# Bolt.net
KiCad netlist of a schematic drawn in EAGLE
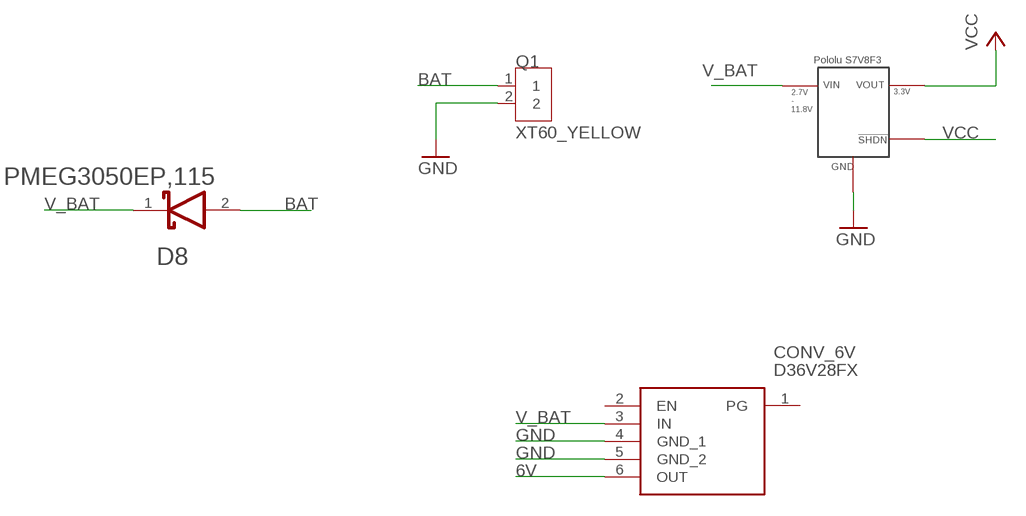
[diagram p0: schematic, sheet 1]
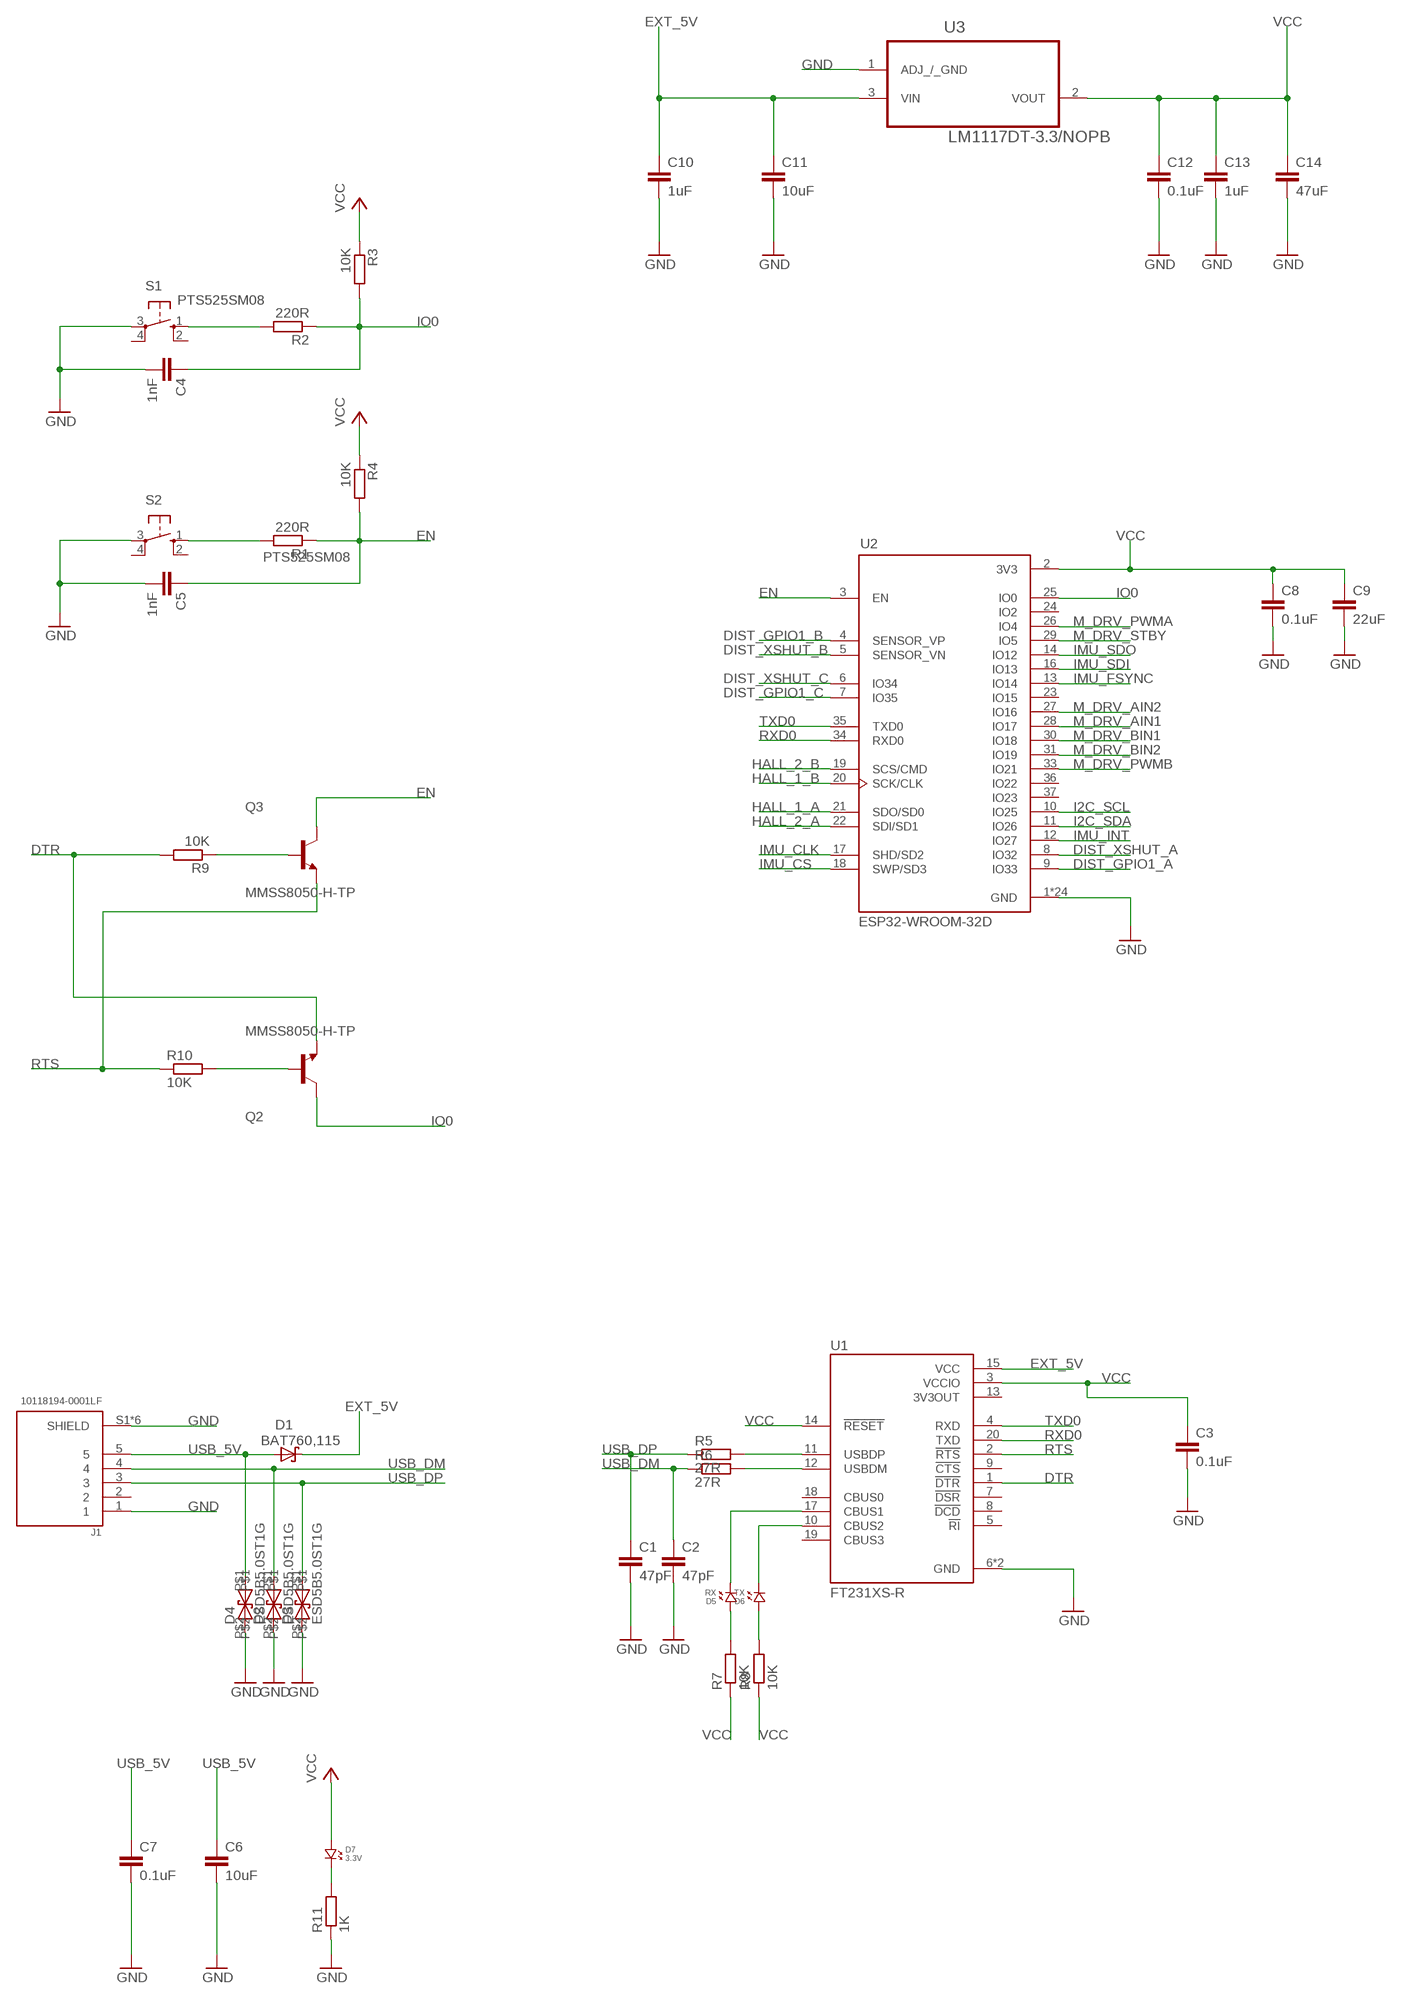
[diagram p1: schematic, sheet 2]
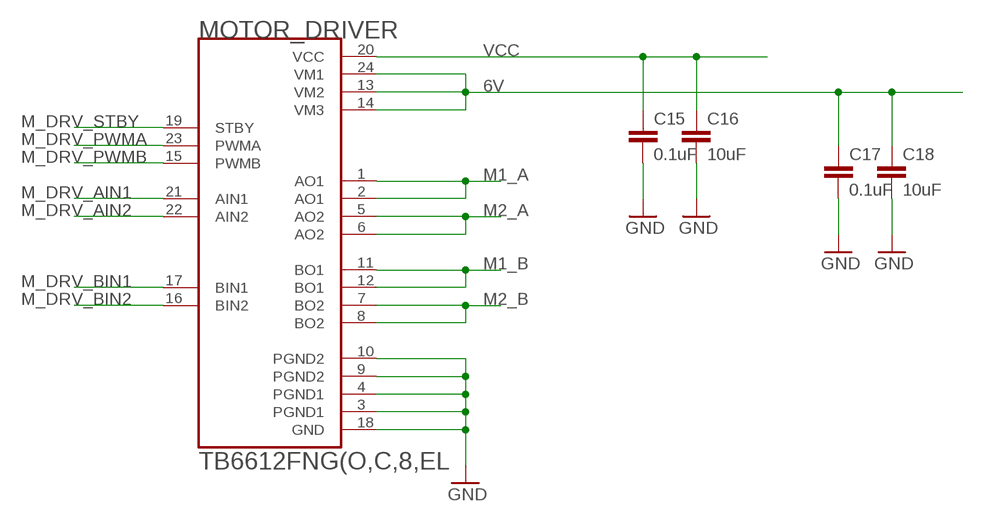
[diagram p2: schematic, sheet 3]
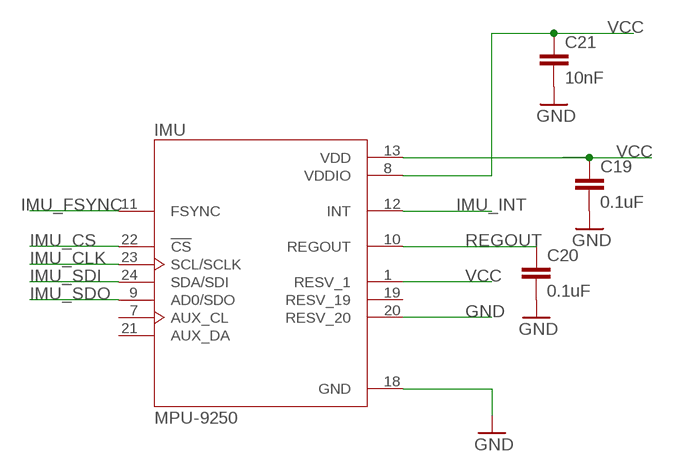
[diagram p3: schematic, sheet 4]
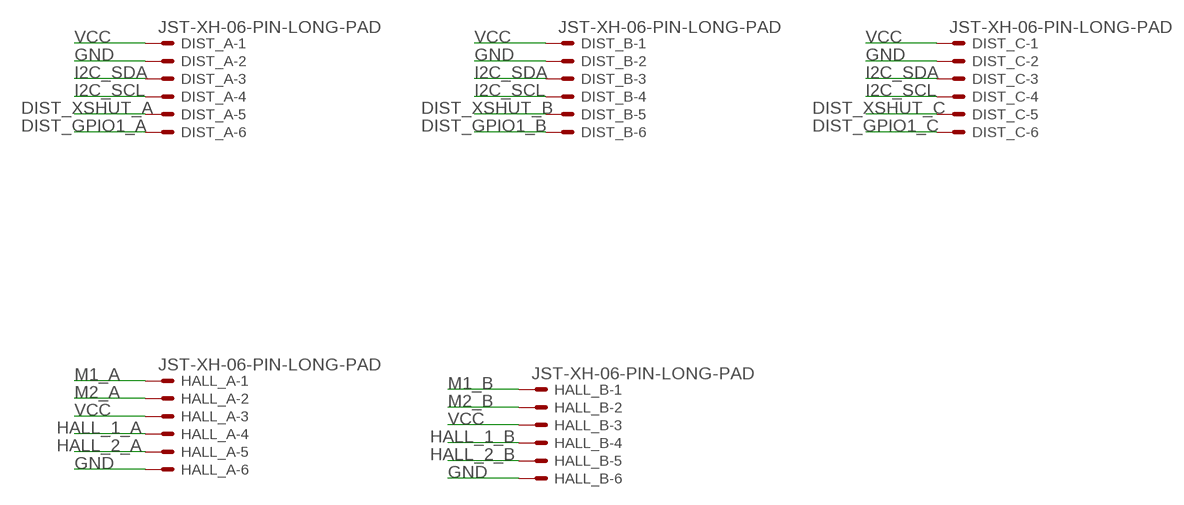
[diagram p4: schematic, sheet 5]

(export (version "E")
  (design (tool "Eeschema 10.0.6"))
  (components
    (comp (ref "C19")
      (value "0.1uF")
      (footprint "eagle-import:C0805K")
      (libsource (lib "eagle-import") (part "C-EUC0805K"))
    )
    (comp (ref "C20")
      (value "0.1uF")
      (footprint "eagle-import:C0805K")
      (libsource (lib "eagle-import") (part "C-EUC0805K"))
    )
    (comp (ref "C21")
      (value "10nF")
      (footprint "eagle-import:C0805K")
      (libsource (lib "eagle-import") (part "C-EUC0805K"))
    )
    (comp (ref "IMU")
      (value "MPU-9250")
      (footprint "eagle-import:QFN40P300X300X105-24N")
      (fields (field (name "MF") "TDK InvenSense"))
      (libsource (lib "eagle-import") (part "MPU-9250"))
    )
    (comp (ref "C1")
      (value "47pF")
      (footprint "eagle-import:C0805K")
      (libsource (lib "eagle-import") (part "C-EUC0805K"))
    )
    (comp (ref "C2")
      (value "47pF")
      (footprint "eagle-import:C0805K")
      (libsource (lib "eagle-import") (part "C-EUC0805K"))
    )
    (comp (ref "C3")
      (value "0.1uF")
      (footprint "eagle-import:C0805K")
      (libsource (lib "eagle-import") (part "C-EUC0805K"))
    )
    (comp (ref "C4")
      (value "1nF")
      (footprint "eagle-import:C0805K")
      (libsource (lib "eagle-import") (part "C-EUC0805K"))
    )
    (comp (ref "C5")
      (value "1nF")
      (footprint "eagle-import:C0805K")
      (libsource (lib "eagle-import") (part "C-EUC0805K"))
    )
    (comp (ref "C6")
      (value "10uF")
      (footprint "eagle-import:C0805K")
      (libsource (lib "eagle-import") (part "C-EUC0805K"))
    )
    (comp (ref "C7")
      (value "0.1uF")
      (footprint "eagle-import:C0805K")
      (libsource (lib "eagle-import") (part "C-EUC0805K"))
    )
    (comp (ref "C8")
      (value "0.1uF")
      (footprint "eagle-import:C0805K")
      (libsource (lib "eagle-import") (part "C-EUC0805K"))
    )
    (comp (ref "C9")
      (value "22uF")
      (footprint "eagle-import:C0805K")
      (libsource (lib "eagle-import") (part "C-EUC0805K"))
    )
    (comp (ref "C10")
      (value "1uF")
      (footprint "eagle-import:C0805K")
      (libsource (lib "eagle-import") (part "C-EUC0805K"))
    )
    (comp (ref "C11")
      (value "10uF")
      (footprint "eagle-import:C0805K")
      (libsource (lib "eagle-import") (part "C-EUC0805K"))
    )
    (comp (ref "C12")
      (value "0.1uF")
      (footprint "eagle-import:C0805K")
      (libsource (lib "eagle-import") (part "C-EUC0805K"))
    )
    (comp (ref "C13")
      (value "1uF")
      (footprint "eagle-import:C0805K")
      (libsource (lib "eagle-import") (part "C-EUC0805K"))
    )
    (comp (ref "C14")
      (value "47uF")
      (footprint "eagle-import:C0805K")
      (libsource (lib "eagle-import") (part "C-EUC0805K"))
    )
    (comp (ref "D1")
      (value "BAT760,115")
      (footprint "eagle-import:SOD323(F)")
      (fields (field (name "MF") "Nexperia USA"))
      (libsource (lib "eagle-import") (part "BAT760,115"))
    )
    (comp (ref "D2")
      (value "ESD5B5.0ST1G")
      (footprint "eagle-import:SOD-523")
      (fields (field (name "MF") "Nexperia USA") (field (name "MP") "BAT760,115"))
      (libsource (lib "eagle-import") (part "ESD5B5.0ST1G"))
    )
    (comp (ref "D3")
      (value "ESD5B5.0ST1G")
      (footprint "eagle-import:SOD-523")
      (fields (field (name "MF") "Nexperia USA") (field (name "MP") "BAT760,115"))
      (libsource (lib "eagle-import") (part "ESD5B5.0ST1G"))
    )
    (comp (ref "D4")
      (value "ESD5B5.0ST1G")
      (footprint "eagle-import:SOD-523")
      (fields (field (name "MF") "Nexperia USA") (field (name "MP") "BAT760,115"))
      (libsource (lib "eagle-import") (part "ESD5B5.0ST1G"))
    )
    (comp (ref "D5")
      (value "RX")
      (footprint "eagle-import:0805.LED")
      (libsource (lib "eagle-import") (part "LED.0805"))
    )
    (comp (ref "D6")
      (value "TX")
      (footprint "eagle-import:0805.LED")
      (libsource (lib "eagle-import") (part "LED.0805"))
    )
    (comp (ref "D7")
      (value "3.3V")
      (footprint "eagle-import:0805.LED")
      (libsource (lib "eagle-import") (part "LED.0805"))
    )
    (comp (ref "J1")
      (value "10118194-0001LF")
      (footprint "eagle-import:AMPHENOL_10118194-0001LF")
      (fields (field (name "MF") "Amphenol ICC (FCI)"))
      (libsource (lib "eagle-import") (part "10118194-0001LF"))
    )
    (comp (ref "Q2")
      (value "MMSS8050-H-TP")
      (footprint "eagle-import:TRANS_MMSS8050-H-TP")
      (fields (field (name "MF") "Micro Commercial"))
      (libsource (lib "eagle-import") (part "MMSS8050-H-TP"))
    )
    (comp (ref "Q3")
      (value "MMSS8050-H-TP")
      (footprint "eagle-import:TRANS_MMSS8050-H-TP")
      (fields (field (name "MF") "Micro Commercial"))
      (libsource (lib "eagle-import") (part "MMSS8050-H-TP"))
    )
    (comp (ref "R1")
      (value "220R")
      (footprint "eagle-import:R0805")
      (libsource (lib "eagle-import") (part "R-EU_R0805"))
    )
    (comp (ref "R2")
      (value "220R")
      (footprint "eagle-import:R0805")
      (libsource (lib "eagle-import") (part "R-EU_R0805"))
    )
    (comp (ref "R3")
      (value "10K")
      (footprint "eagle-import:R0805")
      (libsource (lib "eagle-import") (part "R-EU_R0805"))
    )
    (comp (ref "R4")
      (value "10K")
      (footprint "eagle-import:R0805")
      (libsource (lib "eagle-import") (part "R-EU_R0805"))
    )
    (comp (ref "R5")
      (value "27R")
      (footprint "eagle-import:R0805")
      (libsource (lib "eagle-import") (part "R-EU_R0805"))
    )
    (comp (ref "R6")
      (value "27R")
      (footprint "eagle-import:R0805")
      (libsource (lib "eagle-import") (part "R-EU_R0805"))
    )
    (comp (ref "R7")
      (value "10K")
      (footprint "eagle-import:R0805")
      (libsource (lib "eagle-import") (part "R-EU_R0805"))
    )
    (comp (ref "R8")
      (value "10K")
      (footprint "eagle-import:R0805")
      (libsource (lib "eagle-import") (part "R-EU_R0805"))
    )
    (comp (ref "R9")
      (value "10K")
      (footprint "eagle-import:R0805")
      (libsource (lib "eagle-import") (part "R-EU_R0805"))
    )
    (comp (ref "R10")
      (value "10K")
      (footprint "eagle-import:R0805")
      (libsource (lib "eagle-import") (part "R-EU_R0805"))
    )
    (comp (ref "R11")
      (value "1K")
      (footprint "eagle-import:R0805")
      (libsource (lib "eagle-import") (part "R-EU_R0805"))
    )
    (comp (ref "S1")
      (value "PTS525SM08")
      (footprint "eagle-import:SM08")
      (fields (field (name "MF") "C&K Components") (field (name "MPN") "PTS525SM08SMTR2LFS"))
      (libsource (lib "eagle-import") (part "PTS52508SM"))
    )
    (comp (ref "S2")
      (value "PTS525SM08")
      (footprint "eagle-import:SM08")
      (fields (field (name "MF") "C&K Components") (field (name "MPN") "PTS525SM08SMTR2LFS"))
      (libsource (lib "eagle-import") (part "PTS52508SM"))
    )
    (comp (ref "U1")
      (value "FT231XS-R")
      (footprint "eagle-import:SOP63P599X175-20N")
      (fields (field (name "DIGI-KEY_PART_NUMBER") "768-1129-1-ND") (field (name "MF") "FTDI,"))
      (libsource (lib "eagle-import") (part "FT231XS-R"))
    )
    (comp (ref "U2")
      (value "ESP32-WROOM-32D")
      (footprint "eagle-import:MODULE_ESP32-WROOM-32D")
      (fields (field (name "MF") "Espressif Systems"))
      (libsource (lib "eagle-import") (part "ESP32-WROOM-32D"))
    )
    (comp (ref "U3")
      (value "LM1117DT-3.3/NOPB")
      (footprint "eagle-import:TO228P970X238-3N")
      (fields (field (name "MF") "Texas Instruments"))
      (libsource (lib "eagle-import") (part "LM1117DT-3.3/NOPB"))
    )
    (comp (ref "DIST_A")
      (value "JST-XH-06-PIN-LONG-PAD")
      (footprint "eagle-import:JST-XH-06-PACKAGE-LONG-PAD")
      (libsource (lib "eagle-import") (part "JST-XH-06-PIN-LONG-PAD"))
    )
    (comp (ref "DIST_B")
      (value "JST-XH-06-PIN-LONG-PAD")
      (footprint "eagle-import:JST-XH-06-PACKAGE-LONG-PAD")
      (libsource (lib "eagle-import") (part "JST-XH-06-PIN-LONG-PAD"))
    )
    (comp (ref "DIST_C")
      (value "JST-XH-06-PIN-LONG-PAD")
      (footprint "eagle-import:JST-XH-06-PACKAGE-LONG-PAD")
      (libsource (lib "eagle-import") (part "JST-XH-06-PIN-LONG-PAD"))
    )
    (comp (ref "HALL_A")
      (value "JST-XH-06-PIN-LONG-PAD")
      (footprint "eagle-import:JST-XH-06-PACKAGE-LONG-PAD")
      (libsource (lib "eagle-import") (part "JST-XH-06-PIN-LONG-PAD"))
    )
    (comp (ref "HALL_B")
      (value "JST-XH-06-PIN-LONG-PAD")
      (footprint "eagle-import:JST-XH-06-PACKAGE-LONG-PAD")
      (libsource (lib "eagle-import") (part "JST-XH-06-PIN-LONG-PAD"))
    )
    (comp (ref "C15")
      (value "0.1uF")
      (footprint "eagle-import:C0805K")
      (libsource (lib "eagle-import") (part "C-EUC0805K"))
    )
    (comp (ref "C16")
      (value "10uF")
      (footprint "eagle-import:C0805K")
      (libsource (lib "eagle-import") (part "C-EUC0805K"))
    )
    (comp (ref "C17")
      (value "0.1uF")
      (footprint "eagle-import:C0805K")
      (libsource (lib "eagle-import") (part "C-EUC0805K"))
    )
    (comp (ref "C18")
      (value "10uF")
      (footprint "eagle-import:C0805K")
      (libsource (lib "eagle-import") (part "C-EUC0805K"))
    )
    (comp (ref "MOTOR_DRIVER")
      (value "TB6612FNG(O,C,8,EL")
      (footprint "eagle-import:SOP65P760X160-24N")
      (fields (field (name "MF") "Toshiba"))
      (libsource (lib "eagle-import") (part "TB6612FNG(O,C,8,EL"))
    )
    (comp (ref "CONV_3V3")
      (value "S7V8F3")
      (footprint "eagle-import:S7V8F3")
      (libsource (lib "eagle-import") (part "S7V8F3"))
    )
    (comp (ref "CONV_6V")
      (value "D36V28FX")
      (footprint "eagle-import:D36V28FX")
      (libsource (lib "eagle-import") (part "D36V28FX"))
    )
    (comp (ref "D8")
      (value "NEXPERIA_PMEG3050EP,115NEXPERIA_PMEG3050EP,115_0_0")
      (footprint "eagle-import:NEXPERIA_PMEG3050EP,115_0")
      (fields
        (field (name "DIGIKEY_PART_NUMBER") "1727-5317-1-ND")
        (field (name "MF") "Nexperia")
        (field (name "MOUSER_PART_NUMBER") "771-PMEG3050EP115")
      )
      (libsource (lib "eagle-import") (part "NEXPERIA_PMEG3050EP,115NEXPERIA_PMEG3050EP,115_0_0"))
    )
    (comp (ref "Q1")
      (value "XT60_YELLOW")
      (footprint "eagle-import:AMASS_XT60PB-M")
      (fields (field (name "MF") "Pololu") (field (name "MP") "XT60 YELLOW"))
      (libsource (lib "eagle-import") (part "XT60_YELLOW"))
    )
  )
  (nets
    (net (code "1") (name "3V3OUT") (class "Default")
      (node (ref "U1") (pin "13") (pinfunction "3V3OUT_13") (pintype "power_in"))
    )
    (net (code "2") (name "6V") (class "Default")
      (node (ref "C17") (pin "1") (pinfunction "1_1") (pintype "passive"))
      (node (ref "C18") (pin "1") (pinfunction "1_1") (pintype "passive"))
      (node (ref "CONV_6V") (pin "6") (pinfunction "OUT_6") (pintype "bidirectional"))
      (node (ref "MOTOR_DRIVER") (pin "13") (pinfunction "VM2_13") (pintype "power_in"))
      (node (ref "MOTOR_DRIVER") (pin "14") (pinfunction "VM3_14") (pintype "power_in"))
      (node (ref "MOTOR_DRIVER") (pin "24") (pinfunction "VM1_24") (pintype "power_in"))
    )
    (net (code "3") (name "BAT") (class "Default")
      (node (ref "D8") (pin "2") (pinfunction "ANODE_2") (pintype "passive"))
      (node (ref "Q1") (pin "1") (pinfunction "1_1") (pintype "passive"))
    )
    (net (code "4") (name "DIST_GPIO1_A") (class "Default")
      (node (ref "DIST_A") (pin "6") (pinfunction "S_6") (pintype "passive"))
      (node (ref "U2") (pin "9") (pinfunction "IO33_9") (pintype "bidirectional"))
    )
    (net (code "5") (name "DIST_GPIO1_B") (class "Default")
      (node (ref "DIST_B") (pin "6") (pinfunction "S_6") (pintype "passive"))
      (node (ref "U2") (pin "4") (pinfunction "SENSOR_VP_4") (pintype "input"))
    )
    (net (code "6") (name "DIST_GPIO1_C") (class "Default")
      (node (ref "DIST_C") (pin "6") (pinfunction "S_6") (pintype "passive"))
      (node (ref "U2") (pin "7") (pinfunction "IO35_7") (pintype "input"))
    )
    (net (code "7") (name "DIST_XSHUT_A") (class "Default")
      (node (ref "DIST_A") (pin "5") (pinfunction "S_5") (pintype "passive"))
      (node (ref "U2") (pin "8") (pinfunction "IO32_8") (pintype "bidirectional"))
    )
    (net (code "8") (name "DIST_XSHUT_B") (class "Default")
      (node (ref "DIST_B") (pin "5") (pinfunction "S_5") (pintype "passive"))
      (node (ref "U2") (pin "5") (pinfunction "SENSOR_VN_5") (pintype "input"))
    )
    (net (code "9") (name "DIST_XSHUT_C") (class "Default")
      (node (ref "DIST_C") (pin "5") (pinfunction "S_5") (pintype "passive"))
      (node (ref "U2") (pin "6") (pinfunction "IO34_6") (pintype "input"))
    )
    (net (code "10") (name "DTR") (class "Default")
      (node (ref "Q2") (pin "2") (pinfunction "E_2") (pintype "passive"))
      (node (ref "R9") (pin "2") (pinfunction "2_2") (pintype "passive"))
      (node (ref "U1") (pin "1") (pinfunction "~{DTR}_1") (pintype "output"))
    )
    (net (code "11") (name "EN") (class "Default")
      (node (ref "C5") (pin "1") (pinfunction "1_1") (pintype "passive"))
      (node (ref "Q3") (pin "3") (pinfunction "C_3") (pintype "passive"))
      (node (ref "R1") (pin "1") (pinfunction "1_1") (pintype "passive"))
      (node (ref "R4") (pin "2") (pinfunction "2_2") (pintype "passive"))
      (node (ref "U2") (pin "3") (pinfunction "EN_3") (pintype "input"))
    )
    (net (code "12") (name "EXT_5V") (class "Default")
      (node (ref "C10") (pin "1") (pinfunction "1_1") (pintype "passive"))
      (node (ref "C11") (pin "1") (pinfunction "1_1") (pintype "passive"))
      (node (ref "D1") (pin "1") (pinfunction "K_1") (pintype "passive"))
      (node (ref "U1") (pin "15") (pinfunction "VCC_15") (pintype "power_in"))
      (node (ref "U3") (pin "3") (pinfunction "VIN_3") (pintype "input"))
    )
    (net (code "13") (name "GND") (class "Default")
      (node (ref "C1") (pin "2") (pinfunction "2_2") (pintype "passive"))
      (node (ref "C10") (pin "2") (pinfunction "2_2") (pintype "passive"))
      (node (ref "C11") (pin "2") (pinfunction "2_2") (pintype "passive"))
      (node (ref "C12") (pin "2") (pinfunction "2_2") (pintype "passive"))
      (node (ref "C13") (pin "2") (pinfunction "2_2") (pintype "passive"))
      (node (ref "C14") (pin "2") (pinfunction "2_2") (pintype "passive"))
      (node (ref "C15") (pin "2") (pinfunction "2_2") (pintype "passive"))
      (node (ref "C16") (pin "2") (pinfunction "2_2") (pintype "passive"))
      (node (ref "C17") (pin "2") (pinfunction "2_2") (pintype "passive"))
      (node (ref "C18") (pin "2") (pinfunction "2_2") (pintype "passive"))
      (node (ref "C19") (pin "2") (pinfunction "2_2") (pintype "passive"))
      (node (ref "C2") (pin "2") (pinfunction "2_2") (pintype "passive"))
      (node (ref "C20") (pin "2") (pinfunction "2_2") (pintype "passive"))
      (node (ref "C21") (pin "2") (pinfunction "2_2") (pintype "passive"))
      (node (ref "C3") (pin "2") (pinfunction "2_2") (pintype "passive"))
      (node (ref "C4") (pin "2") (pinfunction "2_2") (pintype "passive"))
      (node (ref "C5") (pin "2") (pinfunction "2_2") (pintype "passive"))
      (node (ref "C6") (pin "2") (pinfunction "2_2") (pintype "passive"))
      (node (ref "C7") (pin "2") (pinfunction "2_2") (pintype "passive"))
      (node (ref "C8") (pin "2") (pinfunction "2_2") (pintype "passive"))
      (node (ref "C9") (pin "2") (pinfunction "2_2") (pintype "passive"))
      (node (ref "CONV_3V3") (pin "GND") (pinfunction "GND_GND") (pintype "bidirectional"))
      (node (ref "CONV_6V") (pin "4") (pinfunction "GND_1_4") (pintype "bidirectional"))
      (node (ref "CONV_6V") (pin "5") (pinfunction "GND_2_5") (pintype "bidirectional"))
      (node (ref "D2") (pin "P$2") (pinfunction "P$1_P$2") (pintype "bidirectional"))
      (node (ref "D3") (pin "P$2") (pinfunction "P$1_P$2") (pintype "bidirectional"))
      (node (ref "D4") (pin "P$2") (pinfunction "P$1_P$2") (pintype "bidirectional"))
      (node (ref "DIST_A") (pin "2") (pinfunction "S_2") (pintype "passive"))
      (node (ref "DIST_B") (pin "2") (pinfunction "S_2") (pintype "passive"))
      (node (ref "DIST_C") (pin "2") (pinfunction "S_2") (pintype "passive"))
      (node (ref "HALL_A") (pin "6") (pinfunction "S_6") (pintype "passive"))
      (node (ref "HALL_B") (pin "6") (pinfunction "S_6") (pintype "passive"))
      (node (ref "IMU") (pin "18") (pinfunction "GND_18") (pintype "power_in"))
      (node (ref "IMU") (pin "20") (pinfunction "RESV_20_20") (pintype "passive"))
      (node (ref "J1") (pin "1") (pinfunction "1_1") (pintype "passive"))
      (node (ref "J1") (pin "S1") (pinfunction "SHIELD_S1") (pintype "passive"))
      (node (ref "J1") (pin "S2") (pinfunction "SHIELD_S2") (pintype "passive"))
      (node (ref "J1") (pin "S3") (pinfunction "SHIELD_S3") (pintype "passive"))
      (node (ref "J1") (pin "S4") (pinfunction "SHIELD_S4") (pintype "passive"))
      (node (ref "J1") (pin "S5") (pinfunction "SHIELD_S5") (pintype "passive"))
      (node (ref "J1") (pin "S6") (pinfunction "SHIELD_S6") (pintype "passive"))
      (node (ref "MOTOR_DRIVER") (pin "10") (pinfunction "PGND2_10") (pintype "passive"))
      (node (ref "MOTOR_DRIVER") (pin "18") (pinfunction "GND_18") (pintype "passive"))
      (node (ref "MOTOR_DRIVER") (pin "3") (pinfunction "PGND1_3") (pintype "passive"))
      (node (ref "MOTOR_DRIVER") (pin "4") (pinfunction "PGND1_4") (pintype "passive"))
      (node (ref "MOTOR_DRIVER") (pin "9") (pinfunction "PGND2_9") (pintype "passive"))
      (node (ref "Q1") (pin "2") (pinfunction "2_2") (pintype "passive"))
      (node (ref "R11") (pin "1") (pinfunction "1_1") (pintype "passive"))
      (node (ref "S1") (pin "3") (pinfunction "P_3") (pintype "passive"))
      (node (ref "S2") (pin "3") (pinfunction "P_3") (pintype "passive"))
      (node (ref "U1") (pin "16") (pinfunction "GND_16") (pintype "power_in"))
      (node (ref "U1") (pin "6") (pinfunction "GND_6") (pintype "power_in"))
      (node (ref "U2") (pin "1") (pinfunction "GND_1") (pintype "power_in"))
      (node (ref "U2") (pin "15") (pinfunction "GND_15") (pintype "power_in"))
      (node (ref "U2") (pin "38") (pinfunction "GND_38") (pintype "power_in"))
      (node (ref "U2") (pin "39_1") (pinfunction "GND_39_1") (pintype "power_in"))
      (node (ref "U2") (pin "39_10") (pinfunction "GND_39_10") (pintype "power_in"))
      (node (ref "U2") (pin "39_11") (pinfunction "GND_39_11") (pintype "power_in"))
      (node (ref "U2") (pin "39_12") (pinfunction "GND_39_12") (pintype "power_in"))
      (node (ref "U2") (pin "39_13") (pinfunction "GND_39_13") (pintype "power_in"))
      (node (ref "U2") (pin "39_14") (pinfunction "GND_39_14") (pintype "power_in"))
      (node (ref "U2") (pin "39_15") (pinfunction "GND_39_15") (pintype "power_in"))
      (node (ref "U2") (pin "39_16") (pinfunction "GND_39_16") (pintype "power_in"))
      (node (ref "U2") (pin "39_17") (pinfunction "GND_39_17") (pintype "power_in"))
      (node (ref "U2") (pin "39_18") (pinfunction "GND_39_18") (pintype "power_in"))
      (node (ref "U2") (pin "39_19") (pinfunction "GND_39_19") (pintype "power_in"))
      (node (ref "U2") (pin "39_2") (pinfunction "GND_39_2") (pintype "power_in"))
      (node (ref "U2") (pin "39_20") (pinfunction "GND_39_20") (pintype "power_in"))
      (node (ref "U2") (pin "39_21") (pinfunction "GND_39_21") (pintype "power_in"))
      (node (ref "U2") (pin "39_3") (pinfunction "GND_39_3") (pintype "power_in"))
      (node (ref "U2") (pin "39_4") (pinfunction "GND_39_4") (pintype "power_in"))
      (node (ref "U2") (pin "39_5") (pinfunction "GND_39_5") (pintype "power_in"))
      (node (ref "U2") (pin "39_6") (pinfunction "GND_39_6") (pintype "power_in"))
      (node (ref "U2") (pin "39_7") (pinfunction "GND_39_7") (pintype "power_in"))
      (node (ref "U2") (pin "39_8") (pinfunction "GND_39_8") (pintype "power_in"))
      (node (ref "U2") (pin "39_9") (pinfunction "GND_39_9") (pintype "power_in"))
      (node (ref "U3") (pin "1") (pinfunction "ADJ_/_GND_1") (pintype "power_in"))
    )
    (net (code "14") (name "HALL_1_A") (class "Default")
      (node (ref "HALL_A") (pin "4") (pinfunction "S_4") (pintype "passive"))
      (node (ref "U2") (pin "21") (pinfunction "SDO/SD0_21") (pintype "bidirectional"))
    )
    (net (code "15") (name "HALL_1_B") (class "Default")
      (node (ref "HALL_B") (pin "4") (pinfunction "S_4") (pintype "passive"))
      (node (ref "U2") (pin "20") (pinfunction "SCK/CLK_20") (pintype "bidirectional"))
    )
    (net (code "16") (name "HALL_2_A") (class "Default")
      (node (ref "HALL_A") (pin "5") (pinfunction "S_5") (pintype "passive"))
      (node (ref "U2") (pin "22") (pinfunction "SDI/SD1_22") (pintype "bidirectional"))
    )
    (net (code "17") (name "HALL_2_B") (class "Default")
      (node (ref "HALL_B") (pin "5") (pinfunction "S_5") (pintype "passive"))
      (node (ref "U2") (pin "19") (pinfunction "SCS/CMD_19") (pintype "bidirectional"))
    )
    (net (code "18") (name "I2C_SCL") (class "Default")
      (node (ref "DIST_A") (pin "4") (pinfunction "S_4") (pintype "passive"))
      (node (ref "DIST_B") (pin "4") (pinfunction "S_4") (pintype "passive"))
      (node (ref "DIST_C") (pin "4") (pinfunction "S_4") (pintype "passive"))
      (node (ref "U2") (pin "10") (pinfunction "IO25_10") (pintype "bidirectional"))
    )
    (net (code "19") (name "I2C_SDA") (class "Default")
      (node (ref "DIST_A") (pin "3") (pinfunction "S_3") (pintype "passive"))
      (node (ref "DIST_B") (pin "3") (pinfunction "S_3") (pintype "passive"))
      (node (ref "DIST_C") (pin "3") (pinfunction "S_3") (pintype "passive"))
      (node (ref "U2") (pin "11") (pinfunction "IO26_11") (pintype "bidirectional"))
    )
    (net (code "20") (name "IMU_CLK") (class "Default")
      (node (ref "IMU") (pin "23") (pinfunction "SCL/SCLK_23") (pintype "input"))
      (node (ref "U2") (pin "17") (pinfunction "SHD/SD2_17") (pintype "bidirectional"))
    )
    (net (code "21") (name "IMU_CS") (class "Default")
      (node (ref "IMU") (pin "22") (pinfunction "~{CS}_22") (pintype "input"))
      (node (ref "U2") (pin "18") (pinfunction "SWP/SD3_18") (pintype "bidirectional"))
    )
    (net (code "22") (name "IMU_FSYNC") (class "Default")
      (node (ref "IMU") (pin "11") (pinfunction "FSYNC_11") (pintype "input"))
      (node (ref "U2") (pin "13") (pinfunction "IO14_13") (pintype "bidirectional"))
    )
    (net (code "23") (name "IMU_INT") (class "Default")
      (node (ref "IMU") (pin "12") (pinfunction "INT_12") (pintype "output"))
      (node (ref "U2") (pin "12") (pinfunction "IO27_12") (pintype "bidirectional"))
    )
    (net (code "24") (name "IMU_SDI") (class "Default")
      (node (ref "IMU") (pin "24") (pinfunction "SDA/SDI_24") (pintype "bidirectional"))
      (node (ref "U2") (pin "16") (pinfunction "IO13_16") (pintype "bidirectional"))
    )
    (net (code "25") (name "IMU_SDO") (class "Default")
      (node (ref "IMU") (pin "9") (pinfunction "AD0/SDO_9") (pintype "output"))
      (node (ref "U2") (pin "14") (pinfunction "IO12_14") (pintype "bidirectional"))
    )
    (net (code "26") (name "IO0") (class "Default")
      (node (ref "C4") (pin "1") (pinfunction "1_1") (pintype "passive"))
      (node (ref "Q2") (pin "3") (pinfunction "C_3") (pintype "passive"))
      (node (ref "R2") (pin "1") (pinfunction "1_1") (pintype "passive"))
      (node (ref "R3") (pin "2") (pinfunction "2_2") (pintype "passive"))
      (node (ref "U2") (pin "25") (pinfunction "IO0_25") (pintype "bidirectional"))
    )
    (net (code "27") (name "M1_A") (class "Default")
      (node (ref "HALL_A") (pin "1") (pinfunction "S_1") (pintype "passive"))
      (node (ref "MOTOR_DRIVER") (pin "1") (pinfunction "AO1_1") (pintype "output"))
      (node (ref "MOTOR_DRIVER") (pin "2") (pinfunction "AO1_2") (pintype "output"))
    )
    (net (code "28") (name "M1_B") (class "Default")
      (node (ref "HALL_B") (pin "1") (pinfunction "S_1") (pintype "passive"))
      (node (ref "MOTOR_DRIVER") (pin "11") (pinfunction "BO1_11") (pintype "output"))
      (node (ref "MOTOR_DRIVER") (pin "12") (pinfunction "BO1_12") (pintype "output"))
    )
    (net (code "29") (name "M2_A") (class "Default")
      (node (ref "HALL_A") (pin "2") (pinfunction "S_2") (pintype "passive"))
      (node (ref "MOTOR_DRIVER") (pin "5") (pinfunction "AO2_5") (pintype "output"))
      (node (ref "MOTOR_DRIVER") (pin "6") (pinfunction "AO2_6") (pintype "output"))
    )
    (net (code "30") (name "M2_B") (class "Default")
      (node (ref "HALL_B") (pin "2") (pinfunction "S_2") (pintype "passive"))
      (node (ref "MOTOR_DRIVER") (pin "7") (pinfunction "BO2_7") (pintype "output"))
      (node (ref "MOTOR_DRIVER") (pin "8") (pinfunction "BO2_8") (pintype "output"))
    )
    (net (code "31") (name "M_DRV_AIN1") (class "Default")
      (node (ref "MOTOR_DRIVER") (pin "21") (pinfunction "AIN1_21") (pintype "input"))
      (node (ref "U2") (pin "28") (pinfunction "IO17_28") (pintype "bidirectional"))
    )
    (net (code "32") (name "M_DRV_AIN2") (class "Default")
      (node (ref "MOTOR_DRIVER") (pin "22") (pinfunction "AIN2_22") (pintype "input"))
      (node (ref "U2") (pin "27") (pinfunction "IO16_27") (pintype "bidirectional"))
    )
    (net (code "33") (name "M_DRV_BIN1") (class "Default")
      (node (ref "MOTOR_DRIVER") (pin "17") (pinfunction "BIN1_17") (pintype "input"))
      (node (ref "U2") (pin "30") (pinfunction "IO18_30") (pintype "bidirectional"))
    )
    (net (code "34") (name "M_DRV_BIN2") (class "Default")
      (node (ref "MOTOR_DRIVER") (pin "16") (pinfunction "BIN2_16") (pintype "input"))
      (node (ref "U2") (pin "31") (pinfunction "IO19_31") (pintype "bidirectional"))
    )
    (net (code "35") (name "M_DRV_PWMA") (class "Default")
      (node (ref "MOTOR_DRIVER") (pin "23") (pinfunction "PWMA_23") (pintype "input"))
      (node (ref "U2") (pin "26") (pinfunction "IO4_26") (pintype "bidirectional"))
    )
    (net (code "36") (name "M_DRV_PWMB") (class "Default")
      (node (ref "MOTOR_DRIVER") (pin "15") (pinfunction "PWMB_15") (pintype "input"))
      (node (ref "U2") (pin "33") (pinfunction "IO21_33") (pintype "bidirectional"))
    )
    (net (code "37") (name "M_DRV_STBY") (class "Default")
      (node (ref "MOTOR_DRIVER") (pin "19") (pinfunction "STBY_19") (pintype "input"))
      (node (ref "U2") (pin "29") (pinfunction "IO5_29") (pintype "bidirectional"))
    )
    (net (code "38") (name "Net-(D5-1)") (class "Default")
      (node (ref "D5") (pin "P$1") (pinfunction "1_P$1") (pintype "bidirectional"))
      (node (ref "R7") (pin "2") (pinfunction "2_2") (pintype "passive"))
    )
    (net (code "39") (name "Net-(D5-2)") (class "Default")
      (node (ref "D5") (pin "P$2") (pinfunction "2_P$2") (pintype "bidirectional"))
      (node (ref "U1") (pin "17") (pinfunction "CBUS1_17") (pintype "bidirectional"))
    )
    (net (code "40") (name "Net-(D6-1)") (class "Default")
      (node (ref "D6") (pin "P$1") (pinfunction "1_P$1") (pintype "bidirectional"))
      (node (ref "R8") (pin "2") (pinfunction "2_2") (pintype "passive"))
    )
    (net (code "41") (name "Net-(D6-2)") (class "Default")
      (node (ref "D6") (pin "P$2") (pinfunction "2_P$2") (pintype "bidirectional"))
      (node (ref "U1") (pin "10") (pinfunction "CBUS2_10") (pintype "bidirectional"))
    )
    (net (code "42") (name "Net-(D7-2)") (class "Default")
      (node (ref "D7") (pin "P$2") (pinfunction "2_P$2") (pintype "bidirectional"))
      (node (ref "R11") (pin "2") (pinfunction "2_2") (pintype "passive"))
    )
    (net (code "43") (name "Net-(Q2-B)") (class "Default")
      (node (ref "Q2") (pin "1") (pinfunction "B_1") (pintype "passive"))
      (node (ref "R10") (pin "2") (pinfunction "2_2") (pintype "passive"))
    )
    (net (code "44") (name "Net-(Q3-B)") (class "Default")
      (node (ref "Q3") (pin "1") (pinfunction "B_1") (pintype "passive"))
      (node (ref "R9") (pin "1") (pinfunction "1_1") (pintype "passive"))
    )
    (net (code "45") (name "Net-(R1-Pad2)") (class "Default")
      (node (ref "R1") (pin "2") (pinfunction "2_2") (pintype "passive"))
      (node (ref "S2") (pin "1") (pinfunction "S_1") (pintype "passive"))
    )
    (net (code "46") (name "Net-(R2-Pad2)") (class "Default")
      (node (ref "R2") (pin "2") (pinfunction "2_2") (pintype "passive"))
      (node (ref "S1") (pin "1") (pinfunction "S_1") (pintype "passive"))
    )
    (net (code "47") (name "Net-(U1-USBDM)") (class "Default")
      (node (ref "R6") (pin "2") (pinfunction "2_2") (pintype "passive"))
      (node (ref "U1") (pin "12") (pinfunction "USBDM_12") (pintype "input"))
    )
    (net (code "48") (name "Net-(U1-USBDP)") (class "Default")
      (node (ref "R5") (pin "2") (pinfunction "2_2") (pintype "passive"))
      (node (ref "U1") (pin "11") (pinfunction "USBDP_11") (pintype "input"))
    )
    (net (code "49") (name "REGOUT") (class "Default")
      (node (ref "C20") (pin "1") (pinfunction "1_1") (pintype "passive"))
      (node (ref "IMU") (pin "10") (pinfunction "REGOUT_10") (pintype "output"))
    )
    (net (code "50") (name "RTS") (class "Default")
      (node (ref "Q3") (pin "2") (pinfunction "E_2") (pintype "passive"))
      (node (ref "R10") (pin "1") (pinfunction "1_1") (pintype "passive"))
      (node (ref "U1") (pin "2") (pinfunction "~{RTS}_2") (pintype "output"))
    )
    (net (code "51") (name "RXD0") (class "Default")
      (node (ref "U1") (pin "20") (pinfunction "TXD_20") (pintype "output"))
      (node (ref "U2") (pin "34") (pinfunction "RXD0_34") (pintype "bidirectional"))
    )
    (net (code "52") (name "TXD0") (class "Default")
      (node (ref "U1") (pin "4") (pinfunction "RXD_4") (pintype "input"))
      (node (ref "U2") (pin "35") (pinfunction "TXD0_35") (pintype "bidirectional"))
    )
    (net (code "53") (name "USB_5V") (class "Default")
      (node (ref "C6") (pin "1") (pinfunction "1_1") (pintype "passive"))
      (node (ref "C7") (pin "1") (pinfunction "1_1") (pintype "passive"))
      (node (ref "D1") (pin "2") (pinfunction "A_2") (pintype "passive"))
      (node (ref "D4") (pin "P$1") (pinfunction "P$2_P$1") (pintype "bidirectional"))
      (node (ref "J1") (pin "5") (pinfunction "5_5") (pintype "passive"))
    )
    (net (code "54") (name "USB_DM") (class "Default")
      (node (ref "C2") (pin "1") (pinfunction "1_1") (pintype "passive"))
      (node (ref "D2") (pin "P$1") (pinfunction "P$2_P$1") (pintype "bidirectional"))
      (node (ref "J1") (pin "4") (pinfunction "4_4") (pintype "passive"))
      (node (ref "R6") (pin "1") (pinfunction "1_1") (pintype "passive"))
    )
    (net (code "55") (name "USB_DP") (class "Default")
      (node (ref "C1") (pin "1") (pinfunction "1_1") (pintype "passive"))
      (node (ref "D3") (pin "P$1") (pinfunction "P$2_P$1") (pintype "bidirectional"))
      (node (ref "J1") (pin "3") (pinfunction "3_3") (pintype "passive"))
      (node (ref "R5") (pin "1") (pinfunction "1_1") (pintype "passive"))
    )
    (net (code "56") (name "VCC") (class "Default")
      (node (ref "C12") (pin "1") (pinfunction "1_1") (pintype "passive"))
      (node (ref "C13") (pin "1") (pinfunction "1_1") (pintype "passive"))
      (node (ref "C14") (pin "1") (pinfunction "1_1") (pintype "passive"))
      (node (ref "C15") (pin "1") (pinfunction "1_1") (pintype "passive"))
      (node (ref "C16") (pin "1") (pinfunction "1_1") (pintype "passive"))
      (node (ref "C19") (pin "1") (pinfunction "1_1") (pintype "passive"))
      (node (ref "C21") (pin "1") (pinfunction "1_1") (pintype "passive"))
      (node (ref "C3") (pin "1") (pinfunction "1_1") (pintype "passive"))
      (node (ref "C8") (pin "1") (pinfunction "1_1") (pintype "passive"))
      (node (ref "C9") (pin "1") (pinfunction "1_1") (pintype "passive"))
      (node (ref "CONV_3V3") (pin "!SHDN") (pinfunction "~{SHDN}_!SHDN") (pintype "bidirectional"))
      (node (ref "CONV_3V3") (pin "VOUT") (pinfunction "VOUT_VOUT") (pintype "bidirectional"))
      (node (ref "D7") (pin "P$1") (pinfunction "1_P$1") (pintype "bidirectional"))
      (node (ref "DIST_A") (pin "1") (pinfunction "S_1") (pintype "passive"))
      (node (ref "DIST_B") (pin "1") (pinfunction "S_1") (pintype "passive"))
      (node (ref "DIST_C") (pin "1") (pinfunction "S_1") (pintype "passive"))
      (node (ref "HALL_A") (pin "3") (pinfunction "S_3") (pintype "passive"))
      (node (ref "HALL_B") (pin "3") (pinfunction "S_3") (pintype "passive"))
      (node (ref "IMU") (pin "1") (pinfunction "RESV_1_1") (pintype "passive"))
      (node (ref "IMU") (pin "13") (pinfunction "VDD_13") (pintype "power_in"))
      (node (ref "IMU") (pin "8") (pinfunction "VDDIO_8") (pintype "power_in"))
      (node (ref "MOTOR_DRIVER") (pin "20") (pinfunction "VCC_20") (pintype "power_in"))
      (node (ref "R3") (pin "1") (pinfunction "1_1") (pintype "passive"))
      (node (ref "R4") (pin "1") (pinfunction "1_1") (pintype "passive"))
      (node (ref "R7") (pin "1") (pinfunction "1_1") (pintype "passive"))
      (node (ref "R8") (pin "1") (pinfunction "1_1") (pintype "passive"))
      (node (ref "U1") (pin "14") (pinfunction "~{RESET}_14") (pintype "input"))
      (node (ref "U1") (pin "3") (pinfunction "VCCIO_3") (pintype "power_in"))
      (node (ref "U2") (pin "2") (pinfunction "3V3_2") (pintype "power_in"))
      (node (ref "U3") (pin "2") (pinfunction "VOUT_2") (pintype "output"))
    )
    (net (code "57") (name "V_BAT") (class "Default")
      (node (ref "CONV_3V3") (pin "VIN") (pinfunction "VIN_VIN") (pintype "bidirectional"))
      (node (ref "CONV_6V") (pin "3") (pinfunction "IN_3") (pintype "bidirectional"))
      (node (ref "D8") (pin "1") (pinfunction "CATHODE_1") (pintype "passive"))
    )
    (net (code "58") (name "unconnected-(CONV_6V-EN-Pad2)") (class "Default")
      (node (ref "CONV_6V") (pin "2") (pinfunction "EN_2") (pintype "bidirectional"))
    )
    (net (code "59") (name "unconnected-(CONV_6V-PG-Pad1)") (class "Default")
      (node (ref "CONV_6V") (pin "1") (pinfunction "PG_1") (pintype "bidirectional"))
    )
    (net (code "60") (name "unconnected-(IMU-AUX_CL-Pad7)") (class "Default")
      (node (ref "IMU") (pin "7") (pinfunction "AUX_CL_7") (pintype "input"))
    )
    (net (code "61") (name "unconnected-(IMU-AUX_DA-Pad21)") (class "Default")
      (node (ref "IMU") (pin "21") (pinfunction "AUX_DA_21") (pintype "input"))
    )
    (net (code "62") (name "unconnected-(IMU-RESV_19-Pad19)") (class "Default")
      (node (ref "IMU") (pin "19") (pinfunction "RESV_19_19") (pintype "passive"))
    )
    (net (code "63") (name "unconnected-(J1-Pad2)") (class "Default")
      (node (ref "J1") (pin "2") (pinfunction "2_2") (pintype "passive"))
    )
    (net (code "64") (name "unconnected-(S1-P-Pad4)") (class "Default")
      (node (ref "S1") (pin "4") (pinfunction "P_4") (pintype "passive"))
    )
    (net (code "65") (name "unconnected-(S1-S-Pad2)") (class "Default")
      (node (ref "S1") (pin "2") (pinfunction "S_2") (pintype "passive"))
    )
    (net (code "66") (name "unconnected-(S2-P-Pad4)") (class "Default")
      (node (ref "S2") (pin "4") (pinfunction "P_4") (pintype "passive"))
    )
    (net (code "67") (name "unconnected-(S2-S-Pad2)") (class "Default")
      (node (ref "S2") (pin "2") (pinfunction "S_2") (pintype "passive"))
    )
    (net (code "68") (name "unconnected-(U1-CBUS0-Pad18)") (class "Default")
      (node (ref "U1") (pin "18") (pinfunction "CBUS0_18") (pintype "bidirectional"))
    )
    (net (code "69") (name "unconnected-(U1-CBUS3-Pad19)") (class "Default")
      (node (ref "U1") (pin "19") (pinfunction "CBUS3_19") (pintype "bidirectional"))
    )
    (net (code "70") (name "unconnected-(U1-~{CTS}-Pad9)") (class "Default")
      (node (ref "U1") (pin "9") (pinfunction "~{CTS}_9") (pintype "input"))
    )
    (net (code "71") (name "unconnected-(U1-~{DCD}-Pad8)") (class "Default")
      (node (ref "U1") (pin "8") (pinfunction "~{DCD}_8") (pintype "input"))
    )
    (net (code "72") (name "unconnected-(U1-~{DSR}-Pad7)") (class "Default")
      (node (ref "U1") (pin "7") (pinfunction "~{DSR}_7") (pintype "input"))
    )
    (net (code "73") (name "unconnected-(U1-~{RI}-Pad5)") (class "Default")
      (node (ref "U1") (pin "5") (pinfunction "~{RI}_5") (pintype "input"))
    )
    (net (code "74") (name "unconnected-(U2-IO2-Pad24)") (class "Default")
      (node (ref "U2") (pin "24") (pinfunction "IO2_24") (pintype "bidirectional"))
    )
    (net (code "75") (name "unconnected-(U2-IO15-Pad23)") (class "Default")
      (node (ref "U2") (pin "23") (pinfunction "IO15_23") (pintype "bidirectional"))
    )
    (net (code "76") (name "unconnected-(U2-IO22-Pad36)") (class "Default")
      (node (ref "U2") (pin "36") (pinfunction "IO22_36") (pintype "bidirectional"))
    )
    (net (code "77") (name "unconnected-(U2-IO23-Pad37)") (class "Default")
      (node (ref "U2") (pin "37") (pinfunction "IO23_37") (pintype "bidirectional"))
    )
  )
)
